# flashlight-smd.net
KiCad netlist of a schematic drawn in EAGLE
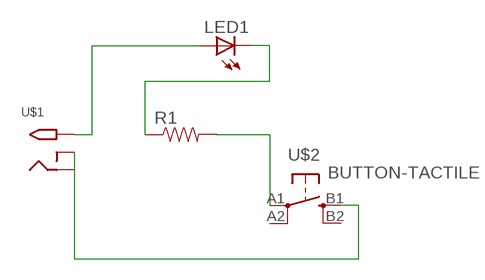
[diagram p0: schematic, sheet 1]

(export (version "E")
  (design (tool "Eeschema 10.0.6"))
  (components
    (comp (ref "LED1")
      (value "LED5MM")
      (footprint "eagle-import:LED5MM")
      (libsource (lib "eagle-import") (part "LED5MM"))
    )
    (comp (ref "R1")
      (value "RESISTORAXIAL-0.3")
      (footprint "eagle-import:AXIAL-0.3")
      (libsource (lib "eagle-import") (part "RESISTORAXIAL-0.3"))
    )
    (comp (ref "U$1")
      (value "2.1MMJACKTHM")
      (footprint "eagle-import:PJ-102A")
      (libsource (lib "eagle-import") (part "2.1MMJACKTHM"))
    )
    (comp (ref "U$2")
      (value "BUTTON-TACTILE")
      (footprint "eagle-import:TACTILE_SWITCH_TALL")
      (libsource (lib "eagle-import") (part "BUTTON-TACTILE"))
    )
  )
  (nets
    (net (code "1") (name "Net-(LED1-C)") (class "Default")
      (node (ref "LED1") (pin "K") (pinfunction "C_K") (pintype "passive"))
      (node (ref "R1") (pin "P$1") (pinfunction "1_P$1") (pintype "passive"))
    )
    (net (code "2") (name "Net-(LED1-PadA)") (class "Default")
      (node (ref "LED1") (pin "A") (pinfunction "A_A") (pintype "passive"))
      (node (ref "U$1") (pin "TIP") (pinfunction "TIP_TIP") (pintype "bidirectional"))
    )
    (net (code "3") (name "Net-(R1-2)") (class "Default")
      (node (ref "R1") (pin "P$2") (pinfunction "2_P$2") (pintype "passive"))
      (node (ref "U$2") (pin "A1") (pinfunction "P_A1") (pintype "passive"))
    )
    (net (code "4") (name "Net-(U$2-S)") (class "Default")
      (node (ref "U$1") (pin "RING") (pinfunction "RING_RING") (pintype "bidirectional"))
      (node (ref "U$1") (pin "RING_SW") (pinfunction "RING_SW_RING_SW") (pintype "bidirectional"))
      (node (ref "U$2") (pin "B1") (pinfunction "S_B1") (pintype "passive"))
    )
    (net (code "5") (name "unconnected-(U$2-P1-PadA2)") (class "Default")
      (node (ref "U$2") (pin "A2") (pinfunction "P1_A2") (pintype "passive"))
    )
    (net (code "6") (name "unconnected-(U$2-S1-PadB2)") (class "Default")
      (node (ref "U$2") (pin "B2") (pinfunction "S1_B2") (pintype "passive"))
    )
  )
)
